# Basic_Sensor_Board.net
KiCad netlist of a schematic drawn in EAGLE
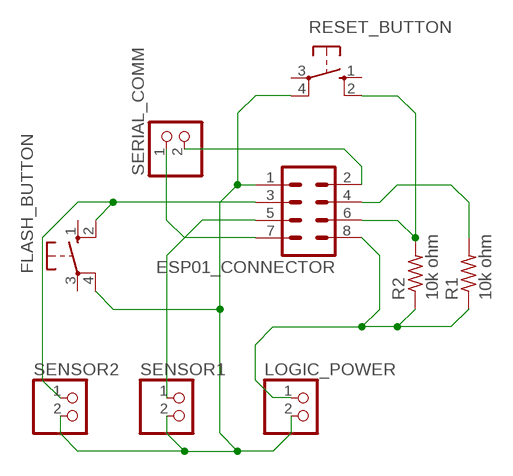
[diagram p0: schematic, sheet 1]

(export (version "E")
  (design (tool "Eeschema 10.0.6"))
  (components
    (comp (ref "ESP01_CONNECTOR")
      (value "MA04-2")
      (footprint "eagle-import:MA04-2")
      (libsource (lib "eagle-import") (part "MA04-2"))
    )
    (comp (ref "FLASH_BUTTON")
      (value "10-XX")
      (footprint "eagle-import:B3F-10XX")
      (fields (field (name "MPN") "B3F-1000"))
      (libsource (lib "eagle-import") (part "10-XX"))
    )
    (comp (ref "LOGIC_POWER")
      (value "PINHD-1X2")
      (footprint "eagle-import:1X02")
      (libsource (lib "eagle-import") (part "PINHD-1X2"))
    )
    (comp (ref "R1")
      (value "10k ohm")
      (footprint "eagle-import:0204_7")
      (libsource (lib "eagle-import") (part "R-US_0204/7"))
    )
    (comp (ref "R2")
      (value "10k ohm")
      (footprint "eagle-import:0204_7")
      (libsource (lib "eagle-import") (part "R-US_0204/7"))
    )
    (comp (ref "RESET_BUTTON")
      (value "10-XX")
      (footprint "eagle-import:B3F-10XX")
      (fields (field (name "MPN") "B3F-1000"))
      (libsource (lib "eagle-import") (part "10-XX"))
    )
    (comp (ref "SENSOR1")
      (value "PINHD-1X2")
      (footprint "eagle-import:1X02")
      (libsource (lib "eagle-import") (part "PINHD-1X2"))
    )
    (comp (ref "SENSOR2")
      (value "PINHD-1X2")
      (footprint "eagle-import:1X02")
      (libsource (lib "eagle-import") (part "PINHD-1X2"))
    )
    (comp (ref "SERIAL_COMM")
      (value "PINHD-1X2")
      (footprint "eagle-import:1X02")
      (libsource (lib "eagle-import") (part "PINHD-1X2"))
    )
  )
  (nets
    (net (code "1") (name "Net-(ESP01_CONNECTOR-Pad2)") (class "Default")
      (node (ref "ESP01_CONNECTOR") (pin "2") (pinfunction "2_2") (pintype "passive"))
      (node (ref "SERIAL_COMM") (pin "2") (pinfunction "2_2") (pintype "passive"))
    )
    (net (code "2") (name "Net-(ESP01_CONNECTOR-Pad4)") (class "Default")
      (node (ref "ESP01_CONNECTOR") (pin "4") (pinfunction "4_4") (pintype "passive"))
      (node (ref "R1") (pin "2") (pinfunction "2_2") (pintype "passive"))
    )
    (net (code "3") (name "Net-(ESP01_CONNECTOR-Pad5)") (class "Default")
      (node (ref "ESP01_CONNECTOR") (pin "5") (pinfunction "5_5") (pintype "passive"))
      (node (ref "SENSOR1") (pin "1") (pinfunction "1_1") (pintype "passive"))
    )
    (net (code "4") (name "Net-(ESP01_CONNECTOR-Pad7)") (class "Default")
      (node (ref "ESP01_CONNECTOR") (pin "7") (pinfunction "7_7") (pintype "passive"))
      (node (ref "SERIAL_COMM") (pin "1") (pinfunction "1_1") (pintype "passive"))
    )
    (net (code "5") (name "Net-(ESP01_CONNECTOR-Pad8)") (class "Default")
      (node (ref "ESP01_CONNECTOR") (pin "8") (pinfunction "8_8") (pintype "passive"))
      (node (ref "LOGIC_POWER") (pin "1") (pinfunction "1_1") (pintype "passive"))
      (node (ref "R1") (pin "1") (pinfunction "1_1") (pintype "passive"))
      (node (ref "R2") (pin "1") (pinfunction "1_1") (pintype "passive"))
    )
    (net (code "6") (name "Net-(FLASH_BUTTON-P1)") (class "Default")
      (node (ref "ESP01_CONNECTOR") (pin "1") (pinfunction "1_1") (pintype "passive"))
      (node (ref "FLASH_BUTTON") (pin "4") (pinfunction "P1_4") (pintype "passive"))
      (node (ref "LOGIC_POWER") (pin "2") (pinfunction "2_2") (pintype "passive"))
      (node (ref "RESET_BUTTON") (pin "4") (pinfunction "P1_4") (pintype "passive"))
      (node (ref "SENSOR1") (pin "2") (pinfunction "2_2") (pintype "passive"))
      (node (ref "SENSOR2") (pin "2") (pinfunction "2_2") (pintype "passive"))
    )
    (net (code "7") (name "Net-(FLASH_BUTTON-S1)") (class "Default")
      (node (ref "ESP01_CONNECTOR") (pin "3") (pinfunction "3_3") (pintype "passive"))
      (node (ref "FLASH_BUTTON") (pin "2") (pinfunction "S1_2") (pintype "passive"))
      (node (ref "SENSOR2") (pin "1") (pinfunction "1_1") (pintype "passive"))
    )
    (net (code "8") (name "Net-(RESET_BUTTON-S1)") (class "Default")
      (node (ref "ESP01_CONNECTOR") (pin "6") (pinfunction "6_6") (pintype "passive"))
      (node (ref "R2") (pin "2") (pinfunction "2_2") (pintype "passive"))
      (node (ref "RESET_BUTTON") (pin "2") (pinfunction "S1_2") (pintype "passive"))
    )
    (net (code "9") (name "unconnected-(FLASH_BUTTON-P-Pad3)") (class "Default")
      (node (ref "FLASH_BUTTON") (pin "3") (pinfunction "P_3") (pintype "passive"))
    )
    (net (code "10") (name "unconnected-(FLASH_BUTTON-S-Pad1)") (class "Default")
      (node (ref "FLASH_BUTTON") (pin "1") (pinfunction "S_1") (pintype "passive"))
    )
    (net (code "11") (name "unconnected-(RESET_BUTTON-P-Pad3)") (class "Default")
      (node (ref "RESET_BUTTON") (pin "3") (pinfunction "P_3") (pintype "passive"))
    )
    (net (code "12") (name "unconnected-(RESET_BUTTON-S-Pad1)") (class "Default")
      (node (ref "RESET_BUTTON") (pin "1") (pinfunction "S_1") (pintype "passive"))
    )
  )
)
